# Power.net
KiCad netlist of a schematic drawn in Altium Designer
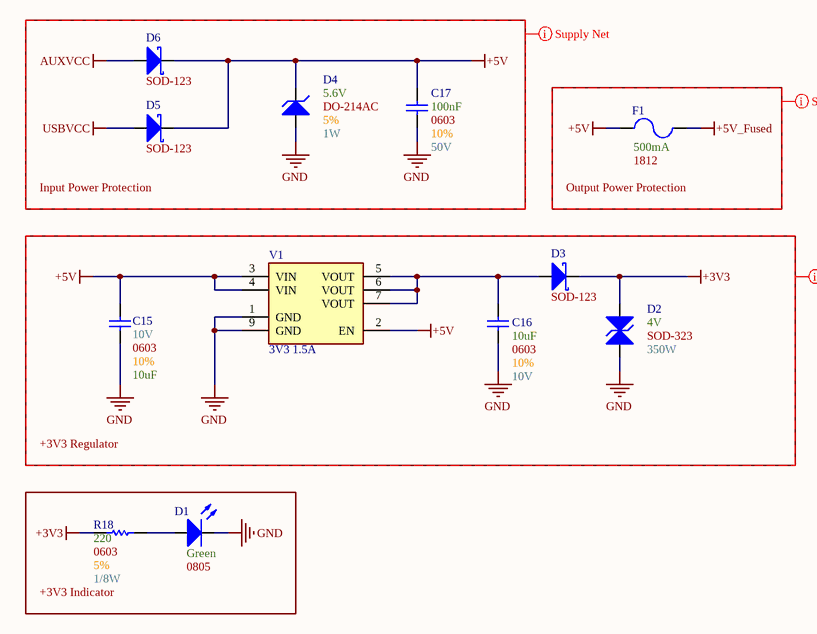
[diagram p0: Power.SchDoc]

(export (version "E")
  (design (tool "Eeschema 10.0.6"))
  (components
    (comp (ref "C15")
      (value "[Cap] 0603 10uF 10% 10V")
      (footprint "[Cap] SMD 0603")
      (description "CL10A106KP8NNNC")
      (fields
        (field (name "MAX VOLTAGE") "10V")
        (field (name "SIZE PACKAGE") "0603")
        (field (name "TOLERANCE") "10%")
        (field (name "CAPACITANCE") "10uF")
      )
      (libsource (lib "Capacitors") (part "[Cap] 0603 10uF 10% 10V"))
    )
    (comp (ref "C16")
      (value "[Cap] 0603 10uF 10% 10V")
      (footprint "[Cap] SMD 0603")
      (description "CL10A106KP8NNNC")
      (fields
        (field (name "MAX VOLTAGE") "10V")
        (field (name "SIZE PACKAGE") "0603")
        (field (name "TOLERANCE") "10%")
        (field (name "CAPACITANCE") "10uF")
      )
      (libsource (lib "Capacitors") (part "[Cap] 0603 10uF 10% 10V"))
    )
    (comp (ref "C17")
      (value "[Cap] 0603 0.1uF 10% 50V")
      (footprint "[Cap] SMD 0603")
      (description "CL10B104KB8NNNC")
      (fields
        (field (name "MAX VOLTAGE") "50V")
        (field (name "SIZE PACKAGE") "0603")
        (field (name "TOLERANCE") "10%")
        (field (name "CAPACITANCE") "100nF")
      )
      (libsource (lib "Capacitors") (part "[Cap] 0603 0.1uF 10% 50V"))
    )
    (comp (ref "D1")
      (value "[LED] SMD 0805 Green")
      (footprint "[LED] SMD 0805")
      (description "LG R971-KN-1-0-20-R18")
      (fields (field (name "COLOR") "Green") (field (name "SIZE PACKAGE") "0805"))
      (libsource (lib "LEDs") (part "[LED] SMD 0805 Green"))
    )
    (comp (ref "D2")
      (value "SOD-323")
      (footprint "SOD-323")
      (description "CDSOD323-T03C")
      (fields (field (name "WATTAGE") "350W") (field (name "OPTIMAL ZENER VOLTAGE") "4V"))
      (libsource (lib "Diodes") (part "[TVS] 3.3Vnom 19Vclamp_max"))
    )
    (comp (ref "D3")
      (value "SOD123")
      (footprint "SOD-123")
      (description "B5819W-TP")
      (libsource (lib "Diodes") (part "[Schottky] SMD 40V 1A"))
    )
    (comp (ref "D4")
      (value "DO-214AC")
      (footprint "DO-214AC")
      (description "SMAZ5V6-13-F")
      (fields
        (field (name "TOLERANCE") "5%")
        (field (name "WATTAGE") "1W")
        (field (name "OPTIMAL ZENER VOLTAGE") "5.6V")
      )
      (libsource (lib "Diodes") (part "[Zener] SMD 5.6V 1W 5%"))
    )
    (comp (ref "D5")
      (value "SOD123")
      (footprint "SOD-123")
      (description "B5819W-TP")
      (libsource (lib "Diodes") (part "[Schottky] SMD 40V 1A"))
    )
    (comp (ref "D6")
      (value "SOD123")
      (footprint "SOD-123")
      (description "B5819W-TP")
      (libsource (lib "Diodes") (part "[Schottky] SMD 40V 1A"))
    )
    (comp (ref "F1")
      (value "[PTC] SMD 1812 500mA")
      (footprint "[PTC] SMD 1812")
      (description "MF-MSMF050-2")
      (fields (field (name "SIZE PACKAGE") "1812") (field (name "TRIP CURRENT") "500mA"))
      (libsource (lib "Fuses") (part "[PTC] SMD 1812 500mA"))
    )
    (comp (ref "R18")
      (value "[220] SMD 0603 5% 1/10W")
      (footprint "[Res] SMD 0603")
      (description "RK73B1JTTD221J")
      (fields
        (field (name "WATTAGE") "1/8W")
        (field (name "TOLERANCE") "5%")
        (field (name "RESISTANCE") "220")
        (field (name "SIZE PACKAGE") "0603")
      )
      (libsource (lib "Resistors") (part "[220] SMD 0603 5% 1/10W"))
    )
    (comp (ref "V1")
      (value "3V3 1.5A")
      (footprint "[Linear] 3V3 1.5A")
      (description "AP7362A-33SP-13")
      (libsource (lib "Voltage Regulators") (part "[Linear] SMD 3V3 1.5A"))
    )
  )
  (nets
    (net (code "1") (name "+3V3") (class "Default")
      (node (ref "D2") (pin "1") (pinfunction "K_1") (pintype "passive"))
      (node (ref "D3") (pin "1") (pinfunction "K_1") (pintype "passive"))
      (node (ref "R18") (pin "1") (pinfunction "1_1") (pintype "passive"))
    )
    (net (code "2") (name "+5V") (class "Default")
      (node (ref "C15") (pin "2") (pinfunction "2_2") (pintype "passive"))
      (node (ref "C17") (pin "2") (pinfunction "2_2") (pintype "passive"))
      (node (ref "D4") (pin "1") (pinfunction "K_1") (pintype "passive"))
      (node (ref "D5") (pin "1") (pinfunction "K_1") (pintype "passive"))
      (node (ref "D6") (pin "1") (pinfunction "K_1") (pintype "passive"))
      (node (ref "F1") (pin "1") (pinfunction "1_1") (pintype "passive"))
      (node (ref "V1") (pin "2") (pinfunction "EN_2") (pintype "passive"))
      (node (ref "V1") (pin "3") (pinfunction "VIN_3") (pintype "passive"))
      (node (ref "V1") (pin "4") (pinfunction "VIN_4") (pintype "passive"))
    )
    (net (code "3") (name "+5V_Fused") (class "Default")
      (node (ref "F1") (pin "2") (pinfunction "2_2") (pintype "passive"))
    )
    (net (code "4") (name "AUXVCC") (class "Default")
      (node (ref "D6") (pin "2") (pinfunction "A_2") (pintype "passive"))
    )
    (net (code "5") (name "GND") (class "Default")
      (node (ref "C15") (pin "1") (pinfunction "1_1") (pintype "passive"))
      (node (ref "C16") (pin "1") (pinfunction "1_1") (pintype "passive"))
      (node (ref "C17") (pin "1") (pinfunction "1_1") (pintype "passive"))
      (node (ref "D1") (pin "2") (pinfunction "Cathode_2") (pintype "passive"))
      (node (ref "D2") (pin "2") (pinfunction "A_2") (pintype "passive"))
      (node (ref "D4") (pin "2") (pinfunction "A_2") (pintype "passive"))
      (node (ref "V1") (pin "1") (pinfunction "GND_1") (pintype "passive"))
      (node (ref "V1") (pin "9") (pinfunction "GND_9") (pintype "passive"))
    )
    (net (code "6") (name "Net-(D1-Anode)") (class "Default")
      (node (ref "D1") (pin "1") (pinfunction "Anode_1") (pintype "passive"))
      (node (ref "R18") (pin "2") (pinfunction "2_2") (pintype "passive"))
    )
    (net (code "7") (name "Net-(D3-A)") (class "Default")
      (node (ref "C16") (pin "2") (pinfunction "2_2") (pintype "passive"))
      (node (ref "D3") (pin "2") (pinfunction "A_2") (pintype "passive"))
      (node (ref "V1") (pin "5") (pinfunction "VOUT_5") (pintype "passive"))
      (node (ref "V1") (pin "6") (pinfunction "VOUT_6") (pintype "passive"))
      (node (ref "V1") (pin "7") (pinfunction "VOUT_7") (pintype "passive"))
    )
    (net (code "8") (name "USBVCC") (class "Default")
      (node (ref "D5") (pin "2") (pinfunction "A_2") (pintype "passive"))
    )
  )
)
